# node_with_dpl_and_relay.net
KiCad netlist of a schematic drawn in EAGLE
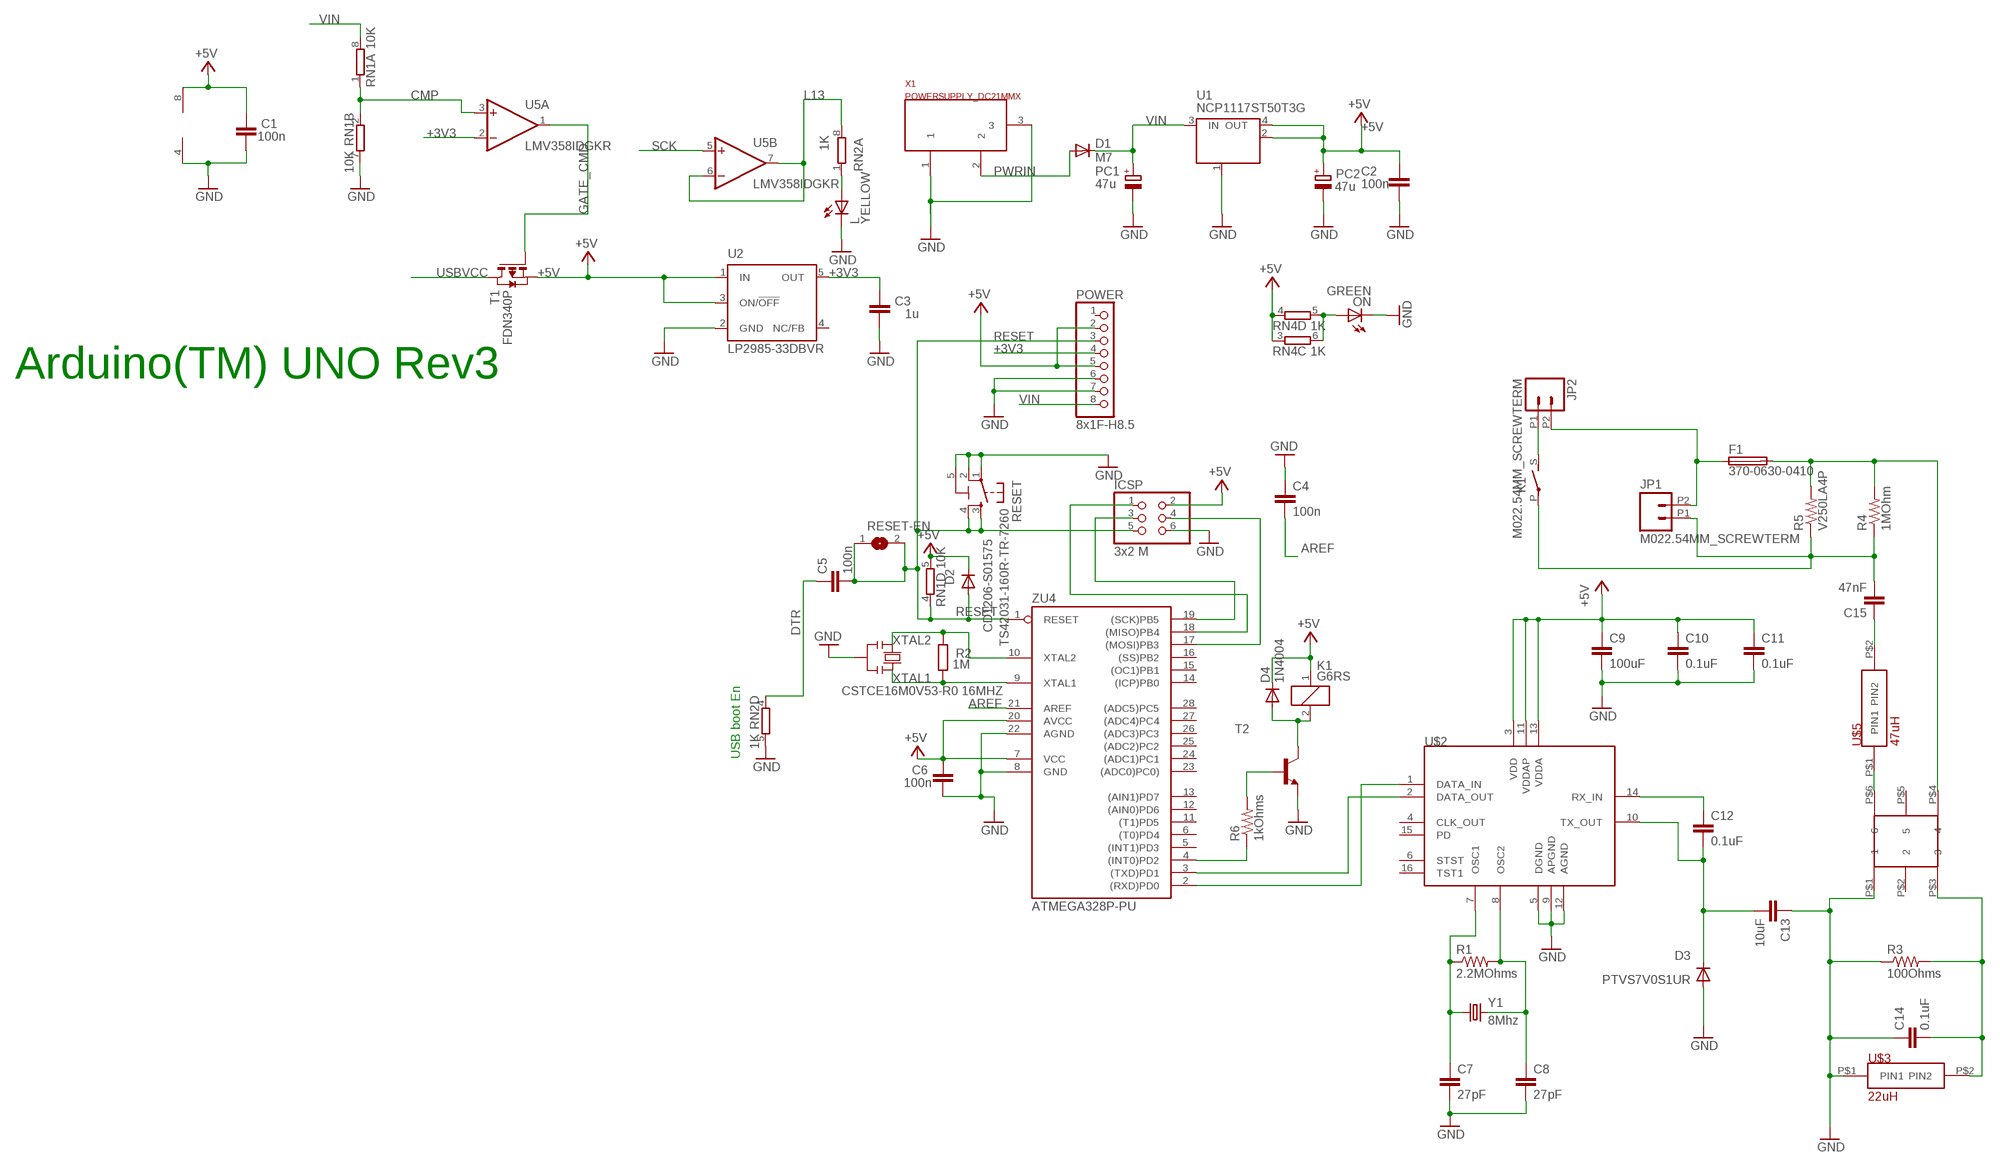
[diagram p0: schematic, sheet 1]

(export (version "E")
  (design (tool "Eeschema 10.0.6"))
  (components
    (comp (ref "C1")
      (value "100n")
      (footprint "eagle-import:C0603-ROUND")
      (libsource (lib "eagle-import") (part "C-EU0603-RND"))
    )
    (comp (ref "C2")
      (value "100n")
      (footprint "eagle-import:C0603-ROUND")
      (libsource (lib "eagle-import") (part "C-EU0603-RND"))
    )
    (comp (ref "C3")
      (value "1u")
      (footprint "eagle-import:C0603-ROUND")
      (libsource (lib "eagle-import") (part "C-EU0603-RND"))
    )
    (comp (ref "C4")
      (value "100n")
      (footprint "eagle-import:C0603-ROUND")
      (libsource (lib "eagle-import") (part "C-EU0603-RND"))
    )
    (comp (ref "C5")
      (value "100n")
      (footprint "eagle-import:C0603-ROUND")
      (libsource (lib "eagle-import") (part "C-EU0603-RND"))
    )
    (comp (ref "C6")
      (value "100n")
      (footprint "eagle-import:C0603-ROUND")
      (libsource (lib "eagle-import") (part "C-EU0603-RND"))
    )
    (comp (ref "C7")
      (value "27pF")
      (footprint "eagle-import:1206")
      (libsource (lib "eagle-import") (part "SparkFun-Passives_CAP1206"))
    )
    (comp (ref "C8")
      (value "27pF")
      (footprint "eagle-import:1206")
      (libsource (lib "eagle-import") (part "SparkFun-Passives_CAP1206"))
    )
    (comp (ref "C9")
      (value "100uF")
      (footprint "eagle-import:1206")
      (libsource (lib "eagle-import") (part "SparkFun-Passives_CAP1206"))
    )
    (comp (ref "C10")
      (value "0.1uF")
      (footprint "eagle-import:1206")
      (libsource (lib "eagle-import") (part "SparkFun-Passives_CAP1206"))
    )
    (comp (ref "C11")
      (value "0.1uF")
      (footprint "eagle-import:1206")
      (libsource (lib "eagle-import") (part "SparkFun-Passives_CAP1206"))
    )
    (comp (ref "C12")
      (value "0.1uF")
      (footprint "eagle-import:AXIAL-5MM")
      (libsource (lib "eagle-import") (part "SparkFun-Passives_CAP_"))
    )
    (comp (ref "C13")
      (value "10uF")
      (footprint "eagle-import:CAP-PTH-SMALL")
      (libsource (lib "eagle-import") (part "CAPPTH"))
    )
    (comp (ref "C14")
      (value "0.1uF")
      (footprint "eagle-import:1206")
      (libsource (lib "eagle-import") (part "SparkFun-Passives_CAP1206"))
    )
    (comp (ref "C15")
      (value "47nF")
      (footprint "eagle-import:C15B5")
      (libsource (lib "eagle-import") (part "C15/5"))
    )
    (comp (ref "D1")
      (value "M7")
      (footprint "eagle-import:SMB")
      (libsource (lib "eagle-import") (part "DIODE-SMB"))
    )
    (comp (ref "D2")
      (value "CD1206-S01575")
      (footprint "eagle-import:MINIMELF")
      (libsource (lib "eagle-import") (part "DIODE-MINIMELF"))
    )
    (comp (ref "D3")
      (value "PTVS7V0S1UR")
      (footprint "eagle-import:SOD-123_MINI-SMA")
      (libsource (lib "eagle-import") (part "CGRM400-G1"))
    )
    (comp (ref "D4")
      (value "1N4004")
      (footprint "eagle-import:DO41-10")
      (libsource (lib "eagle-import") (part "1N4004"))
    )
    (comp (ref "F1")
      (value "370-0630-0410")
      (footprint "eagle-import:TR5")
      (libsource (lib "eagle-import") (part "TR5"))
    )
    (comp (ref "ICSP")
      (value "3x2 M")
      (footprint "eagle-import:2X03")
      (libsource (lib "eagle-import") (part "PINHD-2X3"))
    )
    (comp (ref "JP1")
      (value "M022.54MM_SCREWTERM")
      (footprint "eagle-import:1X02_2.54_SCREWTERM")
      (libsource (lib "eagle-import") (part "M022.54MM_SCREWTERM"))
    )
    (comp (ref "JP2")
      (value "M022.54MM_SCREWTERM")
      (footprint "eagle-import:1X02_2.54_SCREWTERM")
      (libsource (lib "eagle-import") (part "M022.54MM_SCREWTERM"))
    )
    (comp (ref "K1")
      (value "G6RS")
      (footprint "eagle-import:G6RS")
      (libsource (lib "eagle-import") (part "G6RS"))
    )
    (comp (ref "L")
      (value "YELLOW")
      (footprint "eagle-import:CHIP-LED0805")
      (libsource (lib "eagle-import") (part "LEDCHIP-LED0805"))
    )
    (comp (ref "ON")
      (value "GREEN")
      (footprint "eagle-import:CHIP-LED0805")
      (libsource (lib "eagle-import") (part "LEDCHIP-LED0805"))
    )
    (comp (ref "PC1")
      (value "47u")
      (footprint "eagle-import:PANASONIC_D")
      (libsource (lib "eagle-import") (part "CPOL-EUD"))
    )
    (comp (ref "PC2")
      (value "47u")
      (footprint "eagle-import:PANASONIC_D")
      (libsource (lib "eagle-import") (part "CPOL-EUD"))
    )
    (comp (ref "POWER")
      (value "8x1F-H8.5")
      (footprint "eagle-import:1X08")
      (libsource (lib "eagle-import") (part "PINHD-1X8"))
    )
    (comp (ref "R1")
      (value "2.2MOhms")
      (footprint "eagle-import:1206")
      (libsource (lib "eagle-import") (part "RESISTOR1206"))
    )
    (comp (ref "R2")
      (value "1M")
      (footprint "eagle-import:R0603-ROUND")
      (libsource (lib "eagle-import") (part "R-EU_R0603"))
    )
    (comp (ref "R3")
      (value "100Ohms")
      (footprint "eagle-import:AXIAL-0.5")
      (libsource (lib "eagle-import") (part "SparkFun-Resistors_RESISTORPTH-1/2W"))
    )
    (comp (ref "R4")
      (value "1MOhm")
      (footprint "eagle-import:AXIAL-0.3-KIT")
      (libsource (lib "eagle-import") (part "10KOHM1/6W5%(PTH)KIT"))
    )
    (comp (ref "R5")
      (value "V250LA4P")
      (footprint "eagle-import:AXIAL-0.4")
      (libsource (lib "eagle-import") (part "RESISTORPTH-1/4W"))
    )
    (comp (ref "R6")
      (value "1kOhms")
      (footprint "eagle-import:0204V")
      (libsource (lib "eagle-import") (part "R-US_0204/2V"))
    )
    (comp (ref "RESET")
      (value "TS42031-160R-TR-7260")
      (footprint "eagle-import:TS42")
      (libsource (lib "eagle-import") (part "TS42"))
    )
    (comp (ref "RESET-EN")
      (value "SJ")
      (footprint "eagle-import:SJ")
      (libsource (lib "eagle-import") (part "SJ"))
    )
    (comp (ref "RN1")
      (value "10K")
      (footprint "eagle-import:CAY16")
      (libsource (lib "eagle-import") (part "4R-NCAY16"))
    )
    (comp (ref "RN2")
      (value "1K")
      (footprint "eagle-import:CAY16")
      (libsource (lib "eagle-import") (part "4R-NCAY16"))
    )
    (comp (ref "RN4")
      (value "1K")
      (footprint "eagle-import:CAY16")
      (libsource (lib "eagle-import") (part "4R-NCAY16"))
    )
    (comp (ref "T1")
      (value "FDN340P")
      (footprint "eagle-import:SOT-23")
      (libsource (lib "eagle-import") (part "PMOSSOT23"))
    )
    (comp (ref "T2")
      (value "2N5401-NPN-TO92-CBE")
      (footprint "eagle-import:TO92-CBE")
      (libsource (lib "eagle-import") (part "-NPN-TO92-CBE2N5401"))
    )
    (comp (ref "U$2")
      (value "TDA5052AT")
      (footprint "eagle-import:SO16L")
      (libsource (lib "eagle-import") (part "TDA5052AT"))
    )
    (comp (ref "U$3")
      (value "22uH")
      (footprint "eagle-import:RFB0807-220L")
      (libsource (lib "eagle-import") (part "RFB0807-220L"))
    )
    (comp (ref "U$4")
      (value "78250MC")
      (footprint "eagle-import:78250MC")
      (libsource (lib "eagle-import") (part "78250MC"))
    )
    (comp (ref "U$5")
      (value "47uH")
      (footprint "eagle-import:RFB0807-220L")
      (libsource (lib "eagle-import") (part "RFB0807-220L"))
    )
    (comp (ref "U1")
      (value "NCP1117ST50T3G")
      (footprint "eagle-import:SOT223")
      (libsource (lib "eagle-import") (part "MC33269ST-3.3T3"))
    )
    (comp (ref "U2")
      (value "LP2985-33DBVR")
      (footprint "eagle-import:SOT23-DBV")
      (libsource (lib "eagle-import") (part "LP2985-XXDBVR33"))
    )
    (comp (ref "U5")
      (value "LMV358IDGKR")
      (footprint "eagle-import:MSOP08")
      (libsource (lib "eagle-import") (part "LMV358?MMX"))
    )
    (comp (ref "X1")
      (value "POWERSUPPLY_DC21MMX")
      (footprint "eagle-import:POWERSUPPLY_DC-21MM")
      (libsource (lib "eagle-import") (part "POWERSUPPLY_DC21MMX"))
    )
    (comp (ref "Y1")
      (value "8Mhz")
      (footprint "eagle-import:HC49US")
      (libsource (lib "eagle-import") (part "CRYSTALHC49US"))
    )
    (comp (ref "Y2")
      (value "CSTCE16M0V53-R0 16MHZ")
      (footprint "eagle-import:RESONATOR")
      (libsource (lib "eagle-import") (part "RESONATORMU"))
    )
    (comp (ref "ZU4")
      (value "ATMEGA328P-PU")
      (footprint "eagle-import:DIL28-3")
      (libsource (lib "eagle-import") (part "ATMEGA328P-PU"))
    )
  )
  (nets
    (net (code "1") (name "+5V") (class "Default")
      (node (ref "C1") (pin "2") (pinfunction "2_2") (pintype "passive"))
      (node (ref "C10") (pin "1") (pinfunction "1_1") (pintype "passive"))
      (node (ref "C11") (pin "1") (pinfunction "1_1") (pintype "passive"))
      (node (ref "C2") (pin "2") (pinfunction "2_2") (pintype "passive"))
      (node (ref "C6") (pin "2") (pinfunction "2_2") (pintype "passive"))
      (node (ref "C9") (pin "1") (pinfunction "1_1") (pintype "passive"))
      (node (ref "D2") (pin "C") (pinfunction "C_C") (pintype "passive"))
      (node (ref "D4") (pin "C") (pinfunction "C_C") (pintype "passive"))
      (node (ref "ICSP") (pin "2") (pinfunction "2_2") (pintype "passive"))
      (node (ref "K1") (pin "1") (pinfunction "1_1") (pintype "passive"))
      (node (ref "PC2") (pin "+") (pinfunction "+_+") (pintype "passive"))
      (node (ref "POWER") (pin "2") (pinfunction "2_2") (pintype "passive"))
      (node (ref "POWER") (pin "5") (pinfunction "5_5") (pintype "passive"))
      (node (ref "RN1") (pin "5") (pinfunction "2_5") (pintype "passive"))
      (node (ref "RN4") (pin "3") (pinfunction "1_3") (pintype "passive"))
      (node (ref "RN4") (pin "4") (pinfunction "1_4") (pintype "passive"))
      (node (ref "T1") (pin "2") (pinfunction "S_2") (pintype "passive"))
      (node (ref "U$2") (pin "11") (pinfunction "VDDAP_11") (pintype "bidirectional"))
      (node (ref "U$2") (pin "13") (pinfunction "VDDA_13") (pintype "bidirectional"))
      (node (ref "U$2") (pin "3") (pinfunction "VDD_3") (pintype "bidirectional"))
      (node (ref "U1") (pin "2") (pinfunction "OUT_2") (pintype "passive"))
      (node (ref "U1") (pin "4") (pinfunction "OUT_4") (pintype "passive"))
      (node (ref "U2") (pin "1") (pinfunction "IN_1") (pintype "input"))
      (node (ref "U2") (pin "3") (pinfunction "ON/~{OFF}_3") (pintype "input"))
      (node (ref "U5") (pin "8") (pinfunction "V+_8") (pintype "power_in"))
      (node (ref "ZU4") (pin "20") (pinfunction "AVCC_20") (pintype "power_in"))
      (node (ref "ZU4") (pin "7") (pinfunction "VCC_7") (pintype "power_in"))
    )
    (net (code "2") (name "/+3V3") (class "Default")
      (node (ref "C3") (pin "2") (pinfunction "2_2") (pintype "passive"))
      (node (ref "POWER") (pin "4") (pinfunction "4_4") (pintype "passive"))
      (node (ref "U2") (pin "5") (pinfunction "OUT_5") (pintype "passive"))
      (node (ref "U5") (pin "2") (pinfunction "-IN_2") (pintype "input"))
    )
    (net (code "3") (name "/AREF") (class "Default")
      (node (ref "C4") (pin "2") (pinfunction "2_2") (pintype "passive"))
      (node (ref "ZU4") (pin "21") (pinfunction "AREF_21") (pintype "passive"))
    )
    (net (code "4") (name "/CMP") (class "Default")
      (node (ref "RN1") (pin "1") (pinfunction "1_1") (pintype "passive"))
      (node (ref "RN1") (pin "2") (pinfunction "1_2") (pintype "passive"))
      (node (ref "U5") (pin "3") (pinfunction "+IN_3") (pintype "input"))
    )
    (net (code "5") (name "/DTR") (class "Default")
      (node (ref "C5") (pin "1") (pinfunction "1_1") (pintype "passive"))
      (node (ref "RN2") (pin "4") (pinfunction "1_4") (pintype "passive"))
    )
    (net (code "6") (name "/GATE_CMD") (class "Default")
      (node (ref "T1") (pin "3") (pinfunction "G_3") (pintype "passive"))
      (node (ref "U5") (pin "1") (pinfunction "OUT_1") (pintype "output"))
    )
    (net (code "7") (name "/L13") (class "Default")
      (node (ref "RN2") (pin "8") (pinfunction "2_8") (pintype "passive"))
      (node (ref "U5") (pin "6") (pinfunction "-IN_6") (pintype "input"))
      (node (ref "U5") (pin "7") (pinfunction "OUT_7") (pintype "output"))
    )
    (net (code "8") (name "/PWRIN") (class "Default")
      (node (ref "D1") (pin "A") (pinfunction "A_A") (pintype "passive"))
      (node (ref "X1") (pin "2") (pinfunction "2_2") (pintype "power_in"))
    )
    (net (code "9") (name "/RESET") (class "Default")
      (node (ref "C5") (pin "2") (pinfunction "2_2") (pintype "passive"))
      (node (ref "D2") (pin "A") (pinfunction "A_A") (pintype "passive"))
      (node (ref "ICSP") (pin "5") (pinfunction "5_5") (pintype "passive"))
      (node (ref "POWER") (pin "3") (pinfunction "3_3") (pintype "passive"))
      (node (ref "RESET") (pin "3") (pinfunction "3_3") (pintype "passive"))
      (node (ref "RESET") (pin "4") (pinfunction "4_4") (pintype "passive"))
      (node (ref "RESET-EN") (pin "1") (pinfunction "1_1") (pintype "passive"))
      (node (ref "RESET-EN") (pin "2") (pinfunction "2_2") (pintype "passive"))
      (node (ref "RN1") (pin "4") (pinfunction "1_4") (pintype "passive"))
      (node (ref "ZU4") (pin "1") (pinfunction "RESET_1") (pintype "input"))
    )
    (net (code "10") (name "/SCK") (class "Default")
      (node (ref "ICSP") (pin "3") (pinfunction "3_3") (pintype "passive"))
      (node (ref "U5") (pin "5") (pinfunction "+IN_5") (pintype "input"))
      (node (ref "ZU4") (pin "19") (pinfunction "(SCK)PB5_19") (pintype "bidirectional"))
    )
    (net (code "11") (name "/USBVCC") (class "Default")
      (node (ref "T1") (pin "1") (pinfunction "D_1") (pintype "passive"))
    )
    (net (code "12") (name "/VIN") (class "Default")
      (node (ref "D1") (pin "C") (pinfunction "C_C") (pintype "passive"))
      (node (ref "PC1") (pin "+") (pinfunction "+_+") (pintype "passive"))
      (node (ref "POWER") (pin "8") (pinfunction "8_8") (pintype "passive"))
      (node (ref "RN1") (pin "8") (pinfunction "2_8") (pintype "passive"))
      (node (ref "U1") (pin "3") (pinfunction "IN_3") (pintype "input"))
    )
    (net (code "13") (name "/XTAL1") (class "Default")
      (node (ref "R2") (pin "1") (pinfunction "1_1") (pintype "passive"))
      (node (ref "Y2") (pin "3") (pinfunction "3_3") (pintype "passive"))
      (node (ref "ZU4") (pin "9") (pinfunction "XTAL1_9") (pintype "bidirectional"))
    )
    (net (code "14") (name "/XTAL2") (class "Default")
      (node (ref "R2") (pin "2") (pinfunction "2_2") (pintype "passive"))
      (node (ref "Y2") (pin "1") (pinfunction "1_1") (pintype "passive"))
      (node (ref "ZU4") (pin "10") (pinfunction "XTAL2_10") (pintype "bidirectional"))
    )
    (net (code "15") (name "GND") (class "Default")
      (node (ref "C1") (pin "1") (pinfunction "1_1") (pintype "passive"))
      (node (ref "C10") (pin "2") (pinfunction "2_2") (pintype "passive"))
      (node (ref "C11") (pin "2") (pinfunction "2_2") (pintype "passive"))
      (node (ref "C13") (pin "1") (pinfunction "1_1") (pintype "passive"))
      (node (ref "C14") (pin "1") (pinfunction "1_1") (pintype "passive"))
      (node (ref "C2") (pin "1") (pinfunction "1_1") (pintype "passive"))
      (node (ref "C3") (pin "1") (pinfunction "1_1") (pintype "passive"))
      (node (ref "C4") (pin "1") (pinfunction "1_1") (pintype "passive"))
      (node (ref "C6") (pin "1") (pinfunction "1_1") (pintype "passive"))
      (node (ref "C7") (pin "2") (pinfunction "2_2") (pintype "passive"))
      (node (ref "C8") (pin "2") (pinfunction "2_2") (pintype "passive"))
      (node (ref "C9") (pin "2") (pinfunction "2_2") (pintype "passive"))
      (node (ref "D3") (pin "A") (pinfunction "A_A") (pintype "passive"))
      (node (ref "ICSP") (pin "6") (pinfunction "6_6") (pintype "passive"))
      (node (ref "L") (pin "C") (pinfunction "C_C") (pintype "passive"))
      (node (ref "ON") (pin "C") (pinfunction "C_C") (pintype "passive"))
      (node (ref "PC1") (pin "-") (pinfunction "-_-") (pintype "passive"))
      (node (ref "PC2") (pin "-") (pinfunction "-_-") (pintype "passive"))
      (node (ref "POWER") (pin "6") (pinfunction "6_6") (pintype "passive"))
      (node (ref "POWER") (pin "7") (pinfunction "7_7") (pintype "passive"))
      (node (ref "R3") (pin "P$1") (pinfunction "1_P$1") (pintype "passive"))
      (node (ref "RESET") (pin "1") (pinfunction "1_1") (pintype "passive"))
      (node (ref "RESET") (pin "2") (pinfunction "2_2") (pintype "passive"))
      (node (ref "RESET") (pin "5") (pinfunction "5-GND_5") (pintype "power_in"))
      (node (ref "RN1") (pin "7") (pinfunction "2_7") (pintype "passive"))
      (node (ref "RN2") (pin "5") (pinfunction "2_5") (pintype "passive"))
      (node (ref "T2") (pin "E") (pinfunction "E_E") (pintype "passive"))
      (node (ref "U$2") (pin "12") (pinfunction "AGND_12") (pintype "bidirectional"))
      (node (ref "U$2") (pin "5") (pinfunction "DGND_5") (pintype "bidirectional"))
      (node (ref "U$2") (pin "9") (pinfunction "APGND_9") (pintype "bidirectional"))
      (node (ref "U$3") (pin "P$1") (pinfunction "PIN1_P$1") (pintype "bidirectional"))
      (node (ref "U$4") (pin "P$1") (pinfunction "1_P$1") (pintype "bidirectional"))
      (node (ref "U1") (pin "1") (pinfunction "GND/ADJ_1") (pintype "input"))
      (node (ref "U2") (pin "2") (pinfunction "GND_2") (pintype "power_in"))
      (node (ref "U5") (pin "4") (pinfunction "V-_4") (pintype "power_in"))
      (node (ref "X1") (pin "1") (pinfunction "1_1") (pintype "power_in"))
      (node (ref "X1") (pin "3") (pinfunction "3_3") (pintype "power_in"))
      (node (ref "Y2") (pin "2") (pinfunction "2_2") (pintype "passive"))
      (node (ref "ZU4") (pin "22") (pinfunction "AGND_22") (pintype "power_in"))
      (node (ref "ZU4") (pin "8") (pinfunction "GND_8") (pintype "power_in"))
    )
    (net (code "16") (name "Net-(C12-1)") (class "Default")
      (node (ref "C12") (pin "P$1") (pinfunction "1_P$1") (pintype "passive"))
      (node (ref "U$2") (pin "14") (pinfunction "RX_IN_14") (pintype "bidirectional"))
    )
    (net (code "17") (name "Net-(C12-2)") (class "Default")
      (node (ref "C12") (pin "P$2") (pinfunction "2_P$2") (pintype "passive"))
      (node (ref "C13") (pin "2") (pinfunction "2_2") (pintype "passive"))
      (node (ref "D3") (pin "C") (pinfunction "C_C") (pintype "passive"))
      (node (ref "U$2") (pin "10") (pinfunction "TX_OUT_10") (pintype "bidirectional"))
    )
    (net (code "18") (name "Net-(D4-PadA)") (class "Default")
      (node (ref "D4") (pin "A") (pinfunction "A_A") (pintype "passive"))
      (node (ref "K1") (pin "2") (pinfunction "2_2") (pintype "passive"))
      (node (ref "T2") (pin "C") (pinfunction "C_C") (pintype "passive"))
    )
    (net (code "19") (name "Net-(JP1-1)") (class "Default")
      (node (ref "C15") (pin "2") (pinfunction "2_2") (pintype "passive"))
      (node (ref "JP1") (pin "P1") (pinfunction "1_P1") (pintype "passive"))
      (node (ref "K1") (pin "P") (pinfunction "P_P") (pintype "passive"))
      (node (ref "R4") (pin "P$1") (pinfunction "1_P$1") (pintype "passive"))
      (node (ref "R5") (pin "P$1") (pinfunction "1_P$1") (pintype "passive"))
    )
    (net (code "20") (name "Net-(JP1-2)") (class "Default")
      (node (ref "F1") (pin "1") (pinfunction "1_1") (pintype "passive"))
      (node (ref "JP1") (pin "P2") (pinfunction "2_P2") (pintype "passive"))
      (node (ref "JP2") (pin "P2") (pinfunction "2_P2") (pintype "passive"))
    )
    (net (code "21") (name "Net-(JP2-1)") (class "Default")
      (node (ref "JP2") (pin "P1") (pinfunction "1_P1") (pintype "passive"))
      (node (ref "K1") (pin "S") (pinfunction "S_S") (pintype "passive"))
    )
    (net (code "22") (name "Net-(L-PadA)") (class "Default")
      (node (ref "L") (pin "A") (pinfunction "A_A") (pintype "passive"))
      (node (ref "RN2") (pin "1") (pinfunction "1_1") (pintype "passive"))
    )
    (net (code "23") (name "Net-(R3-2)") (class "Default")
      (node (ref "C14") (pin "2") (pinfunction "2_2") (pintype "passive"))
      (node (ref "R3") (pin "P$2") (pinfunction "2_P$2") (pintype "passive"))
      (node (ref "U$3") (pin "P$2") (pinfunction "PIN2_P$2") (pintype "bidirectional"))
      (node (ref "U$4") (pin "P$3") (pinfunction "3_P$3") (pintype "bidirectional"))
    )
    (net (code "24") (name "Net-(R4-2)") (class "Default")
      (node (ref "F1") (pin "2") (pinfunction "2_2") (pintype "passive"))
      (node (ref "R4") (pin "P$2") (pinfunction "2_P$2") (pintype "passive"))
      (node (ref "R5") (pin "P$2") (pinfunction "2_P$2") (pintype "passive"))
      (node (ref "U$4") (pin "P$4") (pinfunction "4_P$4") (pintype "bidirectional"))
    )
    (net (code "25") (name "Net-(R6-Pad2)") (class "Default")
      (node (ref "R6") (pin "2") (pinfunction "2_2") (pintype "passive"))
      (node (ref "T2") (pin "B") (pinfunction "B_B") (pintype "passive"))
    )
    (net (code "26") (name "Net-(RN4C-2)") (class "Default")
      (node (ref "ON") (pin "A") (pinfunction "A_A") (pintype "passive"))
      (node (ref "RN4") (pin "5") (pinfunction "2_5") (pintype "passive"))
      (node (ref "RN4") (pin "6") (pinfunction "2_6") (pintype "passive"))
    )
    (net (code "27") (name "Net-(U$2-DATA_IN)") (class "Default")
      (node (ref "U$2") (pin "1") (pinfunction "DATA_IN_1") (pintype "bidirectional"))
      (node (ref "ZU4") (pin "2") (pinfunction "(RXD)PD0_2") (pintype "bidirectional"))
    )
    (net (code "28") (name "Net-(U$2-DATA_OUT)") (class "Default")
      (node (ref "U$2") (pin "2") (pinfunction "DATA_OUT_2") (pintype "bidirectional"))
      (node (ref "ZU4") (pin "3") (pinfunction "(TXD)PD1_3") (pintype "bidirectional"))
    )
    (net (code "29") (name "Net-(U$2-OSC1)") (class "Default")
      (node (ref "C7") (pin "1") (pinfunction "1_1") (pintype "passive"))
      (node (ref "R1") (pin "1") (pinfunction "1_1") (pintype "passive"))
      (node (ref "U$2") (pin "7") (pinfunction "OSC1_7") (pintype "bidirectional"))
      (node (ref "Y1") (pin "1") (pinfunction "1_1") (pintype "passive"))
    )
    (net (code "30") (name "Net-(U$2-OSC2)") (class "Default")
      (node (ref "C8") (pin "1") (pinfunction "1_1") (pintype "passive"))
      (node (ref "R1") (pin "2") (pinfunction "2_2") (pintype "passive"))
      (node (ref "U$2") (pin "8") (pinfunction "OSC2_8") (pintype "bidirectional"))
      (node (ref "Y1") (pin "2") (pinfunction "2_2") (pintype "passive"))
    )
    (net (code "31") (name "Net-(U$4-6)") (class "Default")
      (node (ref "U$4") (pin "P$6") (pinfunction "6_P$6") (pintype "bidirectional"))
      (node (ref "U$5") (pin "P$1") (pinfunction "PIN1_P$1") (pintype "bidirectional"))
    )
    (net (code "32") (name "Net-(U$5-PIN2)") (class "Default")
      (node (ref "C15") (pin "1") (pinfunction "1_1") (pintype "passive"))
      (node (ref "U$5") (pin "P$2") (pinfunction "PIN2_P$2") (pintype "bidirectional"))
    )
    (net (code "33") (name "Net-(ZU4-(INT0)PD2)") (class "Default")
      (node (ref "R6") (pin "1") (pinfunction "1_1") (pintype "passive"))
      (node (ref "ZU4") (pin "4") (pinfunction "(INT0)PD2_4") (pintype "bidirectional"))
    )
    (net (code "34") (name "Net-(ZU4-(MISO)PB4)") (class "Default")
      (node (ref "ICSP") (pin "1") (pinfunction "1_1") (pintype "passive"))
      (node (ref "ZU4") (pin "18") (pinfunction "(MISO)PB4_18") (pintype "bidirectional"))
    )
    (net (code "35") (name "Net-(ZU4-(MOSI)PB3)") (class "Default")
      (node (ref "ICSP") (pin "4") (pinfunction "4_4") (pintype "passive"))
      (node (ref "ZU4") (pin "17") (pinfunction "(MOSI)PB3_17") (pintype "bidirectional"))
    )
    (net (code "36") (name "unconnected-(POWER-Pad1)") (class "Default")
      (node (ref "POWER") (pin "1") (pinfunction "1_1") (pintype "passive"))
    )
    (net (code "37") (name "unconnected-(U$2-CLK_OUT-Pad4)") (class "Default")
      (node (ref "U$2") (pin "4") (pinfunction "CLK_OUT_4") (pintype "bidirectional"))
    )
    (net (code "38") (name "unconnected-(U$2-PD-Pad15)") (class "Default")
      (node (ref "U$2") (pin "15") (pinfunction "PD_15") (pintype "bidirectional"))
    )
    (net (code "39") (name "unconnected-(U$2-STST-Pad6)") (class "Default")
      (node (ref "U$2") (pin "6") (pinfunction "STST_6") (pintype "bidirectional"))
    )
    (net (code "40") (name "unconnected-(U$2-TST1-Pad16)") (class "Default")
      (node (ref "U$2") (pin "16") (pinfunction "TST1_16") (pintype "bidirectional"))
    )
    (net (code "41") (name "unconnected-(U$4-2-PadP$2)") (class "Default")
      (node (ref "U$4") (pin "P$2") (pinfunction "2_P$2") (pintype "bidirectional"))
    )
    (net (code "42") (name "unconnected-(U$4-5-PadP$5)") (class "Default")
      (node (ref "U$4") (pin "P$5") (pinfunction "5_P$5") (pintype "bidirectional"))
    )
    (net (code "43") (name "unconnected-(U2-NC{slash}FB-Pad4)") (class "Default")
      (node (ref "U2") (pin "4") (pinfunction "NC/FB_4") (pintype "passive"))
    )
    (net (code "44") (name "unconnected-(ZU4-(ADC0)PC0)-Pad23)") (class "Default")
      (node (ref "ZU4") (pin "23") (pinfunction "(ADC0)PC0)_23") (pintype "bidirectional"))
    )
    (net (code "45") (name "unconnected-(ZU4-(ADC1)PC1-Pad24)") (class "Default")
      (node (ref "ZU4") (pin "24") (pinfunction "(ADC1)PC1_24") (pintype "bidirectional"))
    )
    (net (code "46") (name "unconnected-(ZU4-(ADC2)PC2-Pad25)") (class "Default")
      (node (ref "ZU4") (pin "25") (pinfunction "(ADC2)PC2_25") (pintype "bidirectional"))
    )
    (net (code "47") (name "unconnected-(ZU4-(ADC3)PC3-Pad26)") (class "Default")
      (node (ref "ZU4") (pin "26") (pinfunction "(ADC3)PC3_26") (pintype "bidirectional"))
    )
    (net (code "48") (name "unconnected-(ZU4-(ADC4)PC4-Pad27)") (class "Default")
      (node (ref "ZU4") (pin "27") (pinfunction "(ADC4)PC4_27") (pintype "bidirectional"))
    )
    (net (code "49") (name "unconnected-(ZU4-(ADC5)PC5-Pad28)") (class "Default")
      (node (ref "ZU4") (pin "28") (pinfunction "(ADC5)PC5_28") (pintype "bidirectional"))
    )
    (net (code "50") (name "unconnected-(ZU4-(AIN0)PD6-Pad12)") (class "Default")
      (node (ref "ZU4") (pin "12") (pinfunction "(AIN0)PD6_12") (pintype "bidirectional"))
    )
    (net (code "51") (name "unconnected-(ZU4-(AIN1)PD7-Pad13)") (class "Default")
      (node (ref "ZU4") (pin "13") (pinfunction "(AIN1)PD7_13") (pintype "bidirectional"))
    )
    (net (code "52") (name "unconnected-(ZU4-(ICP)PB0-Pad14)") (class "Default")
      (node (ref "ZU4") (pin "14") (pinfunction "(ICP)PB0_14") (pintype "bidirectional"))
    )
    (net (code "53") (name "unconnected-(ZU4-(INT1)PD3-Pad5)") (class "Default")
      (node (ref "ZU4") (pin "5") (pinfunction "(INT1)PD3_5") (pintype "bidirectional"))
    )
    (net (code "54") (name "unconnected-(ZU4-(OC1)PB1-Pad15)") (class "Default")
      (node (ref "ZU4") (pin "15") (pinfunction "(OC1)PB1_15") (pintype "bidirectional"))
    )
    (net (code "55") (name "unconnected-(ZU4-(SS)PB2-Pad16)") (class "Default")
      (node (ref "ZU4") (pin "16") (pinfunction "(SS)PB2_16") (pintype "bidirectional"))
    )
    (net (code "56") (name "unconnected-(ZU4-(T0)PD4-Pad6)") (class "Default")
      (node (ref "ZU4") (pin "6") (pinfunction "(T0)PD4_6") (pintype "bidirectional"))
    )
    (net (code "57") (name "unconnected-(ZU4-(T1)PD5-Pad11)") (class "Default")
      (node (ref "ZU4") (pin "11") (pinfunction "(T1)PD5_11") (pintype "bidirectional"))
    )
  )
)
